# Magnetometer_revb.net
KiCad netlist of a schematic drawn in EAGLE
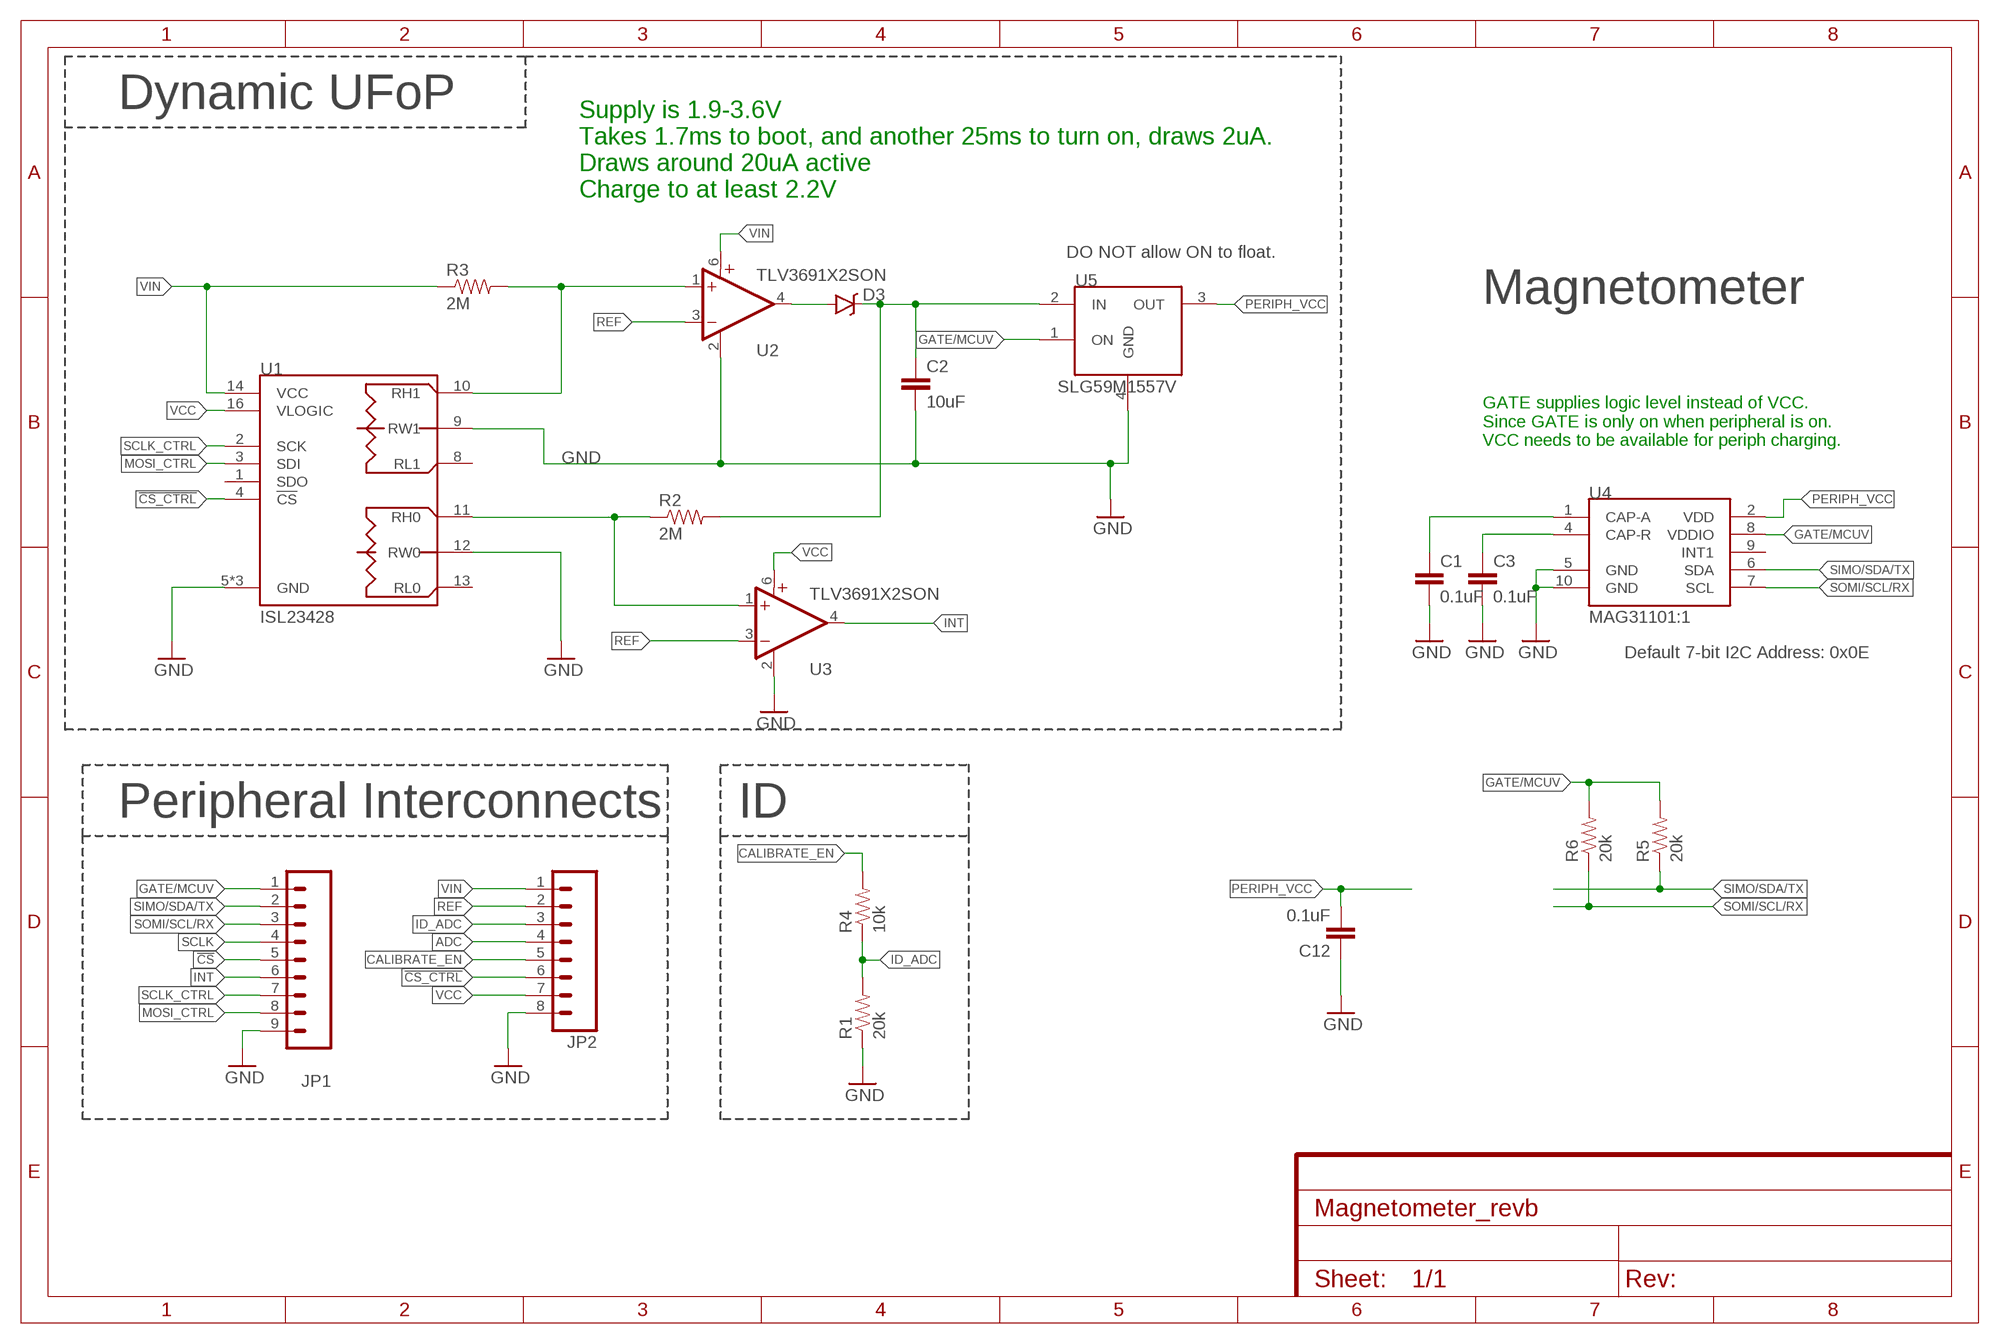
[diagram p0: schematic, sheet 1]

(export (version "E")
  (design (tool "Eeschema 10.0.6"))
  (components
    (comp (ref "C1")
      (value "0.1uF")
      (footprint "eagle-import:0402")
      (fields (field (name "MPN") "  0402YD104KAT2A"))
      (libsource (lib "eagle-import") (part "C-EU"))
    )
    (comp (ref "C2")
      (value "10uF")
      (footprint "eagle-import:0805")
      (fields (field (name "MPN") "GRM21BR60J106ME19L"))
      (libsource (lib "eagle-import") (part "CAP0805"))
    )
    (comp (ref "C3")
      (value "0.1uF")
      (footprint "eagle-import:0402")
      (fields (field (name "MPN") "  0402YD104KAT2A"))
      (libsource (lib "eagle-import") (part "C-EU"))
    )
    (comp (ref "C12")
      (value "0.1uF")
      (footprint "eagle-import:0402")
      (fields (field (name "MPN") "  0402YD104KAT2A"))
      (libsource (lib "eagle-import") (part "C-EU"))
    )
    (comp (ref "D3")
      (value "RB751")
      (footprint "eagle-import:SOD-523")
      (fields (field (name "MPN") "BAS40-02V-V-G-08"))
      (libsource (lib "eagle-import") (part "DIODE-SCHOTTKY-RB751"))
    )
    (comp (ref "JP1")
      (value "M091.27MM")
      (footprint "eagle-import:1X09-1.27MM")
      (fields (field (name "MPN") "GRPB091VWVN-RC "))
      (libsource (lib "eagle-import") (part "M091.27MM"))
    )
    (comp (ref "JP2")
      (value "M081.27MM")
      (footprint "eagle-import:1X08-1.27MM")
      (fields (field (name "MPN") "GRPB081VWVN-RC "))
      (libsource (lib "eagle-import") (part "M081.27MM"))
    )
    (comp (ref "R1")
      (value "20k")
      (footprint "eagle-import:0402")
      (fields (field (name "MPN") "ERJ-2RKF2002X"))
      (libsource (lib "eagle-import") (part "R-EU"))
    )
    (comp (ref "R2")
      (value "2M")
      (footprint "eagle-import:0402")
      (fields (field (name "MPN") "RC1005F205CS"))
      (libsource (lib "eagle-import") (part "R-EU"))
    )
    (comp (ref "R3")
      (value "2M")
      (footprint "eagle-import:0402")
      (fields (field (name "MPN") "RC1005F205CS"))
      (libsource (lib "eagle-import") (part "R-EU"))
    )
    (comp (ref "R4")
      (value "10k")
      (footprint "eagle-import:0402")
      (fields (field (name "MPN") "ERJ-2RKF1002X"))
      (libsource (lib "eagle-import") (part "R-EU"))
    )
    (comp (ref "R5")
      (value "20k")
      (footprint "eagle-import:0603")
      (fields (field (name "MPN") "ERJ-2RKF2002X"))
      (libsource (lib "eagle-import") (part "R-EU0603"))
    )
    (comp (ref "R6")
      (value "20k")
      (footprint "eagle-import:0603")
      (fields (field (name "MPN") "ERJ-2RKF2002X"))
      (libsource (lib "eagle-import") (part "R-EU0603"))
    )
    (comp (ref "U1")
      (value "ISL23428")
      (footprint "eagle-import:UTQFN-16")
      (fields (field (name "MPN") "ISL23428TFRUZ-T7A"))
      (libsource (lib "eagle-import") (part "ISL23428"))
    )
    (comp (ref "U2")
      (value "TLV3691X2SON")
      (footprint "eagle-import:X2SON")
      (fields (field (name "MPN") "TLV3691IDPFR"))
      (libsource (lib "eagle-import") (part "TLV3691X2SON"))
    )
    (comp (ref "U3")
      (value "TLV3691X2SON")
      (footprint "eagle-import:X2SON")
      (fields (field (name "MPN") "TLV3691IDPFR"))
      (libsource (lib "eagle-import") (part "TLV3691X2SON"))
    )
    (comp (ref "U4")
      (value "MAG31101:1")
      (footprint "eagle-import:DFN-10-W")
      (fields (field (name "MPN") "MAG3110FCR1"))
      (libsource (lib "eagle-import") (part "MAG31101{colon}1"))
    )
    (comp (ref "U5")
      (value "SLG59M1557V")
      (footprint "eagle-import:4STDFN")
      (fields (field (name "MPN") "SLG59M1557V "))
      (libsource (lib "eagle-import") (part "SLG59M1557V"))
    )
  )
  (nets
    (net (code "1") (name "/~{CS_CTRL}") (class "Default")
      (node (ref "JP2") (pin "6") (pinfunction "6_6") (pintype "passive"))
      (node (ref "U1") (pin "4") (pinfunction "~{CS}_4") (pintype "bidirectional"))
    )
    (net (code "2") (name "/~{CS}") (class "Default")
      (node (ref "JP1") (pin "5") (pinfunction "5_5") (pintype "passive"))
    )
    (net (code "3") (name "ADC") (class "Default")
      (node (ref "JP2") (pin "4") (pinfunction "4_4") (pintype "passive"))
    )
    (net (code "4") (name "CALIBRATE_EN") (class "Default")
      (node (ref "JP2") (pin "5") (pinfunction "5_5") (pintype "passive"))
      (node (ref "R4") (pin "2") (pinfunction "2_2") (pintype "passive"))
    )
    (net (code "5") (name "GATE{slash}MCUV") (class "Default")
      (node (ref "JP1") (pin "1") (pinfunction "1_1") (pintype "passive"))
      (node (ref "R5") (pin "2") (pinfunction "2_2") (pintype "passive"))
      (node (ref "R6") (pin "2") (pinfunction "2_2") (pintype "passive"))
      (node (ref "U4") (pin "8") (pinfunction "VDDIO_8") (pintype "bidirectional"))
      (node (ref "U5") (pin "1") (pinfunction "ON_1") (pintype "bidirectional"))
    )
    (net (code "6") (name "GND") (class "Default")
      (node (ref "C1") (pin "2") (pinfunction "2_2") (pintype "passive"))
      (node (ref "C12") (pin "1") (pinfunction "1_1") (pintype "passive"))
      (node (ref "C2") (pin "2") (pinfunction "2_2") (pintype "passive"))
      (node (ref "C3") (pin "2") (pinfunction "2_2") (pintype "passive"))
      (node (ref "JP1") (pin "9") (pinfunction "9_9") (pintype "passive"))
      (node (ref "JP2") (pin "8") (pinfunction "8_8") (pintype "passive"))
      (node (ref "R1") (pin "1") (pinfunction "1_1") (pintype "passive"))
      (node (ref "U1") (pin "12") (pinfunction "RW0_12") (pintype "bidirectional"))
      (node (ref "U1") (pin "15") (pinfunction "GND_15") (pintype "bidirectional"))
      (node (ref "U1") (pin "5") (pinfunction "GND_5") (pintype "bidirectional"))
      (node (ref "U1") (pin "6") (pinfunction "GND_6") (pintype "bidirectional"))
      (node (ref "U1") (pin "9") (pinfunction "RW1_9") (pintype "bidirectional"))
      (node (ref "U2") (pin "2") (pinfunction "GND_2") (pintype "power_in"))
      (node (ref "U3") (pin "2") (pinfunction "GND_2") (pintype "power_in"))
      (node (ref "U4") (pin "10") (pinfunction "GND_10") (pintype "bidirectional"))
      (node (ref "U4") (pin "5") (pinfunction "GND_5") (pintype "bidirectional"))
      (node (ref "U5") (pin "4") (pinfunction "GND_4") (pintype "bidirectional"))
    )
    (net (code "7") (name "ID_ADC") (class "Default")
      (node (ref "JP2") (pin "3") (pinfunction "3_3") (pintype "passive"))
      (node (ref "R1") (pin "2") (pinfunction "2_2") (pintype "passive"))
      (node (ref "R4") (pin "1") (pinfunction "1_1") (pintype "passive"))
    )
    (net (code "8") (name "INT") (class "Default")
      (node (ref "JP1") (pin "6") (pinfunction "6_6") (pintype "passive"))
      (node (ref "U3") (pin "4") (pinfunction "OUT_4") (pintype "output"))
    )
    (net (code "9") (name "MOSI_CTRL") (class "Default")
      (node (ref "JP1") (pin "8") (pinfunction "8_8") (pintype "passive"))
      (node (ref "U1") (pin "3") (pinfunction "SDI_3") (pintype "bidirectional"))
    )
    (net (code "10") (name "Net-(U1-RH0)") (class "Default")
      (node (ref "R2") (pin "1") (pinfunction "1_1") (pintype "passive"))
      (node (ref "U1") (pin "11") (pinfunction "RH0_11") (pintype "bidirectional"))
      (node (ref "U3") (pin "1") (pinfunction "+IN_1") (pintype "input"))
    )
    (net (code "11") (name "Net-(U1-RH1)") (class "Default")
      (node (ref "R3") (pin "2") (pinfunction "2_2") (pintype "passive"))
      (node (ref "U1") (pin "10") (pinfunction "RH1_10") (pintype "bidirectional"))
      (node (ref "U2") (pin "1") (pinfunction "+IN_1") (pintype "input"))
    )
    (net (code "12") (name "Net-(U2-OUT)") (class "Default")
      (node (ref "D3") (pin "A") (pinfunction "A_A") (pintype "passive"))
      (node (ref "U2") (pin "4") (pinfunction "OUT_4") (pintype "output"))
    )
    (net (code "13") (name "Net-(U4-CAP-A)") (class "Default")
      (node (ref "C1") (pin "1") (pinfunction "1_1") (pintype "passive"))
      (node (ref "U4") (pin "1") (pinfunction "CAP-A_1") (pintype "bidirectional"))
    )
    (net (code "14") (name "Net-(U4-CAP-R)") (class "Default")
      (node (ref "C3") (pin "1") (pinfunction "1_1") (pintype "passive"))
      (node (ref "U4") (pin "4") (pinfunction "CAP-R_4") (pintype "bidirectional"))
    )
    (net (code "15") (name "Net-(U5-IN)") (class "Default")
      (node (ref "C2") (pin "1") (pinfunction "1_1") (pintype "passive"))
      (node (ref "D3") (pin "C") (pinfunction "C_C") (pintype "passive"))
      (node (ref "R2") (pin "2") (pinfunction "2_2") (pintype "passive"))
      (node (ref "U5") (pin "2") (pinfunction "IN_2") (pintype "bidirectional"))
    )
    (net (code "16") (name "PERIPH_VCC") (class "Default")
      (node (ref "C12") (pin "2") (pinfunction "2_2") (pintype "passive"))
      (node (ref "U4") (pin "2") (pinfunction "VDD_2") (pintype "bidirectional"))
      (node (ref "U5") (pin "3") (pinfunction "OUT_3") (pintype "bidirectional"))
    )
    (net (code "17") (name "REF") (class "Default")
      (node (ref "JP2") (pin "2") (pinfunction "2_2") (pintype "passive"))
      (node (ref "U2") (pin "3") (pinfunction "-IN_3") (pintype "input"))
      (node (ref "U3") (pin "3") (pinfunction "-IN_3") (pintype "input"))
    )
    (net (code "18") (name "SCLK") (class "Default")
      (node (ref "JP1") (pin "4") (pinfunction "4_4") (pintype "passive"))
    )
    (net (code "19") (name "SCLK_CTRL") (class "Default")
      (node (ref "JP1") (pin "7") (pinfunction "7_7") (pintype "passive"))
      (node (ref "U1") (pin "2") (pinfunction "SCK_2") (pintype "bidirectional"))
    )
    (net (code "20") (name "SIMO{slash}SDA{slash}TX") (class "Default")
      (node (ref "JP1") (pin "2") (pinfunction "2_2") (pintype "passive"))
      (node (ref "R5") (pin "1") (pinfunction "1_1") (pintype "passive"))
      (node (ref "U4") (pin "6") (pinfunction "SDA_6") (pintype "bidirectional"))
    )
    (net (code "21") (name "SOMI{slash}SCL{slash}RX") (class "Default")
      (node (ref "JP1") (pin "3") (pinfunction "3_3") (pintype "passive"))
      (node (ref "R6") (pin "1") (pinfunction "1_1") (pintype "passive"))
      (node (ref "U4") (pin "7") (pinfunction "SCL_7") (pintype "bidirectional"))
    )
    (net (code "22") (name "VCC") (class "Default")
      (node (ref "JP2") (pin "7") (pinfunction "7_7") (pintype "passive"))
      (node (ref "U1") (pin "16") (pinfunction "VLOGIC_16") (pintype "bidirectional"))
      (node (ref "U3") (pin "6") (pinfunction "V+_6") (pintype "power_in"))
    )
    (net (code "23") (name "VIN") (class "Default")
      (node (ref "JP2") (pin "1") (pinfunction "1_1") (pintype "passive"))
      (node (ref "R3") (pin "1") (pinfunction "1_1") (pintype "passive"))
      (node (ref "U1") (pin "14") (pinfunction "VCC_14") (pintype "bidirectional"))
      (node (ref "U2") (pin "6") (pinfunction "V+_6") (pintype "power_in"))
    )
    (net (code "24") (name "unconnected-(U1-RL0-Pad13)") (class "Default")
      (node (ref "U1") (pin "13") (pinfunction "RL0_13") (pintype "bidirectional"))
    )
    (net (code "25") (name "unconnected-(U1-RL1-Pad8)") (class "Default")
      (node (ref "U1") (pin "8") (pinfunction "RL1_8") (pintype "bidirectional"))
    )
    (net (code "26") (name "unconnected-(U1-SDO-Pad1)") (class "Default")
      (node (ref "U1") (pin "1") (pinfunction "SDO_1") (pintype "bidirectional"))
    )
    (net (code "27") (name "unconnected-(U4-INT1-Pad9)") (class "Default")
      (node (ref "U4") (pin "9") (pinfunction "INT1_9") (pintype "bidirectional"))
    )
  )
)
